# SolenoidControl.net
KiCad netlist of a schematic drawn in EAGLE
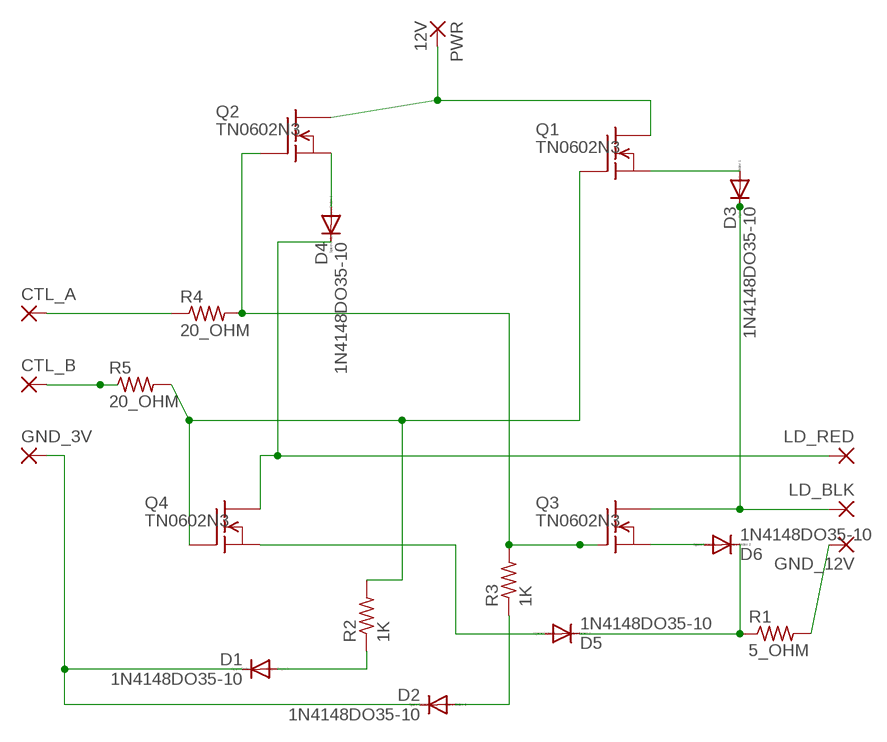
[diagram p0: schematic, sheet 1]

(export (version "E")
  (design (tool "Eeschema 10.0.6"))
  (components
    (comp (ref "CTL_A")
      (value "2,15/1,0")
      (footprint "eagle-import:2,15_1,0")
      (libsource (lib "eagle-import") (part "2,15/1,0"))
    )
    (comp (ref "CTL_B")
      (value "2,15/1,0")
      (footprint "eagle-import:2,15_1,0")
      (libsource (lib "eagle-import") (part "2,15/1,0"))
    )
    (comp (ref "D1")
      (value "1N4148DO35-10")
      (footprint "eagle-import:DO35-10")
      (libsource (lib "eagle-import") (part "1N4148DO35-10"))
    )
    (comp (ref "D2")
      (value "1N4148DO35-10")
      (footprint "eagle-import:DO35-10")
      (libsource (lib "eagle-import") (part "1N4148DO35-10"))
    )
    (comp (ref "D3")
      (value "1N4148DO35-10")
      (footprint "eagle-import:DO35-10")
      (libsource (lib "eagle-import") (part "1N4148DO35-10"))
    )
    (comp (ref "D4")
      (value "1N4148DO35-10")
      (footprint "eagle-import:DO35-10")
      (libsource (lib "eagle-import") (part "1N4148DO35-10"))
    )
    (comp (ref "D5")
      (value "1N4148DO35-10")
      (footprint "eagle-import:DO35-10")
      (libsource (lib "eagle-import") (part "1N4148DO35-10"))
    )
    (comp (ref "D6")
      (value "1N4148DO35-10")
      (footprint "eagle-import:DO35-10")
      (libsource (lib "eagle-import") (part "1N4148DO35-10"))
    )
    (comp (ref "GND_3V")
      (value "2,15/1,0")
      (footprint "eagle-import:2,15_1,0")
      (libsource (lib "eagle-import") (part "2,15/1,0"))
    )
    (comp (ref "GND_12V")
      (value "2,15/1,0")
      (footprint "eagle-import:2,15_1,0")
      (libsource (lib "eagle-import") (part "2,15/1,0"))
    )
    (comp (ref "LD_BLK")
      (value "2,15/1,0")
      (footprint "eagle-import:2,15_1,0")
      (libsource (lib "eagle-import") (part "2,15/1,0"))
    )
    (comp (ref "LD_RED")
      (value "2,15/1,0")
      (footprint "eagle-import:2,15_1,0")
      (libsource (lib "eagle-import") (part "2,15/1,0"))
    )
    (comp (ref "PWR")
      (value "12V")
      (footprint "eagle-import:2,15_1,0")
      (libsource (lib "eagle-import") (part "2,15/1,0"))
    )
    (comp (ref "Q1")
      (value "TN0602N3")
      (footprint "eagle-import:TO-92")
      (libsource (lib "eagle-import") (part "TN0602N3"))
    )
    (comp (ref "Q2")
      (value "TN0602N3")
      (footprint "eagle-import:TO-92")
      (libsource (lib "eagle-import") (part "TN0602N3"))
    )
    (comp (ref "Q3")
      (value "TN0602N3")
      (footprint "eagle-import:TO-92")
      (libsource (lib "eagle-import") (part "TN0602N3"))
    )
    (comp (ref "Q4")
      (value "TN0602N3")
      (footprint "eagle-import:TO-92")
      (libsource (lib "eagle-import") (part "TN0602N3"))
    )
    (comp (ref "R1")
      (value "5_OHM")
      (footprint "eagle-import:0207_12")
      (libsource (lib "eagle-import") (part "R-US_0207/12"))
    )
    (comp (ref "R2")
      (value "1K")
      (footprint "eagle-import:0207_12")
      (libsource (lib "eagle-import") (part "R-US_0207/12"))
    )
    (comp (ref "R3")
      (value "1K")
      (footprint "eagle-import:0207_12")
      (libsource (lib "eagle-import") (part "R-US_0207/12"))
    )
    (comp (ref "R4")
      (value "20_OHM")
      (footprint "eagle-import:0207_12")
      (libsource (lib "eagle-import") (part "R-US_0207/12"))
    )
    (comp (ref "R5")
      (value "20_OHM")
      (footprint "eagle-import:0207_12")
      (libsource (lib "eagle-import") (part "R-US_0207/12"))
    )
  )
  (nets
    (net (code "1") (name "Net-(CTL_A-P)") (class "Default")
      (node (ref "CTL_A") (pin "1") (pinfunction "P_1") (pintype "passive"))
      (node (ref "R4") (pin "1") (pinfunction "1_1") (pintype "passive"))
    )
    (net (code "2") (name "Net-(CTL_B-P)") (class "Default")
      (node (ref "CTL_B") (pin "1") (pinfunction "P_1") (pintype "passive"))
      (node (ref "R5") (pin "1") (pinfunction "1_1") (pintype "passive"))
    )
    (net (code "3") (name "Net-(D1-PadA)") (class "Default")
      (node (ref "D1") (pin "A") (pinfunction "A_A") (pintype "passive"))
      (node (ref "R2") (pin "1") (pinfunction "1_1") (pintype "passive"))
    )
    (net (code "4") (name "Net-(D2-PadA)") (class "Default")
      (node (ref "D2") (pin "A") (pinfunction "A_A") (pintype "passive"))
      (node (ref "R3") (pin "1") (pinfunction "1_1") (pintype "passive"))
    )
    (net (code "5") (name "Net-(D5-PadC)") (class "Default")
      (node (ref "D5") (pin "C") (pinfunction "C_C") (pintype "passive"))
      (node (ref "D6") (pin "C") (pinfunction "C_C") (pintype "passive"))
      (node (ref "R1") (pin "1") (pinfunction "1_1") (pintype "passive"))
    )
    (net (code "6") (name "Net-(GND_3V-P)") (class "Default")
      (node (ref "D1") (pin "C") (pinfunction "C_C") (pintype "passive"))
      (node (ref "D2") (pin "C") (pinfunction "C_C") (pintype "passive"))
      (node (ref "GND_3V") (pin "1") (pinfunction "P_1") (pintype "passive"))
    )
    (net (code "7") (name "Net-(GND_12V-P)") (class "Default")
      (node (ref "GND_12V") (pin "1") (pinfunction "P_1") (pintype "passive"))
      (node (ref "R1") (pin "2") (pinfunction "2_2") (pintype "passive"))
    )
    (net (code "8") (name "Net-(LD_BLK-P)") (class "Default")
      (node (ref "D3") (pin "C") (pinfunction "C_C") (pintype "passive"))
      (node (ref "LD_BLK") (pin "1") (pinfunction "P_1") (pintype "passive"))
      (node (ref "Q3") (pin "3") (pinfunction "D_3") (pintype "passive"))
    )
    (net (code "9") (name "Net-(LD_RED-P)") (class "Default")
      (node (ref "D4") (pin "C") (pinfunction "C_C") (pintype "passive"))
      (node (ref "LD_RED") (pin "1") (pinfunction "P_1") (pintype "passive"))
      (node (ref "Q4") (pin "3") (pinfunction "D_3") (pintype "passive"))
    )
    (net (code "10") (name "Net-(PWR-P)") (class "Default")
      (node (ref "PWR") (pin "1") (pinfunction "P_1") (pintype "passive"))
      (node (ref "Q1") (pin "3") (pinfunction "D_3") (pintype "passive"))
      (node (ref "Q2") (pin "3") (pinfunction "D_3") (pintype "passive"))
    )
    (net (code "11") (name "Net-(Q1-G)") (class "Default")
      (node (ref "Q1") (pin "2") (pinfunction "G_2") (pintype "passive"))
      (node (ref "Q4") (pin "2") (pinfunction "G_2") (pintype "passive"))
      (node (ref "R2") (pin "2") (pinfunction "2_2") (pintype "passive"))
      (node (ref "R5") (pin "2") (pinfunction "2_2") (pintype "passive"))
    )
    (net (code "12") (name "Net-(Q1-S)") (class "Default")
      (node (ref "D3") (pin "A") (pinfunction "A_A") (pintype "passive"))
      (node (ref "Q1") (pin "1") (pinfunction "S_1") (pintype "passive"))
    )
    (net (code "13") (name "Net-(Q2-G)") (class "Default")
      (node (ref "Q2") (pin "2") (pinfunction "G_2") (pintype "passive"))
      (node (ref "Q3") (pin "2") (pinfunction "G_2") (pintype "passive"))
      (node (ref "R3") (pin "2") (pinfunction "2_2") (pintype "passive"))
      (node (ref "R4") (pin "2") (pinfunction "2_2") (pintype "passive"))
    )
    (net (code "14") (name "Net-(Q2-S)") (class "Default")
      (node (ref "D4") (pin "A") (pinfunction "A_A") (pintype "passive"))
      (node (ref "Q2") (pin "1") (pinfunction "S_1") (pintype "passive"))
    )
    (net (code "15") (name "Net-(Q3-S)") (class "Default")
      (node (ref "D6") (pin "A") (pinfunction "A_A") (pintype "passive"))
      (node (ref "Q3") (pin "1") (pinfunction "S_1") (pintype "passive"))
    )
    (net (code "16") (name "Net-(Q4-S)") (class "Default")
      (node (ref "D5") (pin "A") (pinfunction "A_A") (pintype "passive"))
      (node (ref "Q4") (pin "1") (pinfunction "S_1") (pintype "passive"))
    )
  )
)
